# Sheet1.net
KiCad netlist of a schematic drawn in Altium Designer
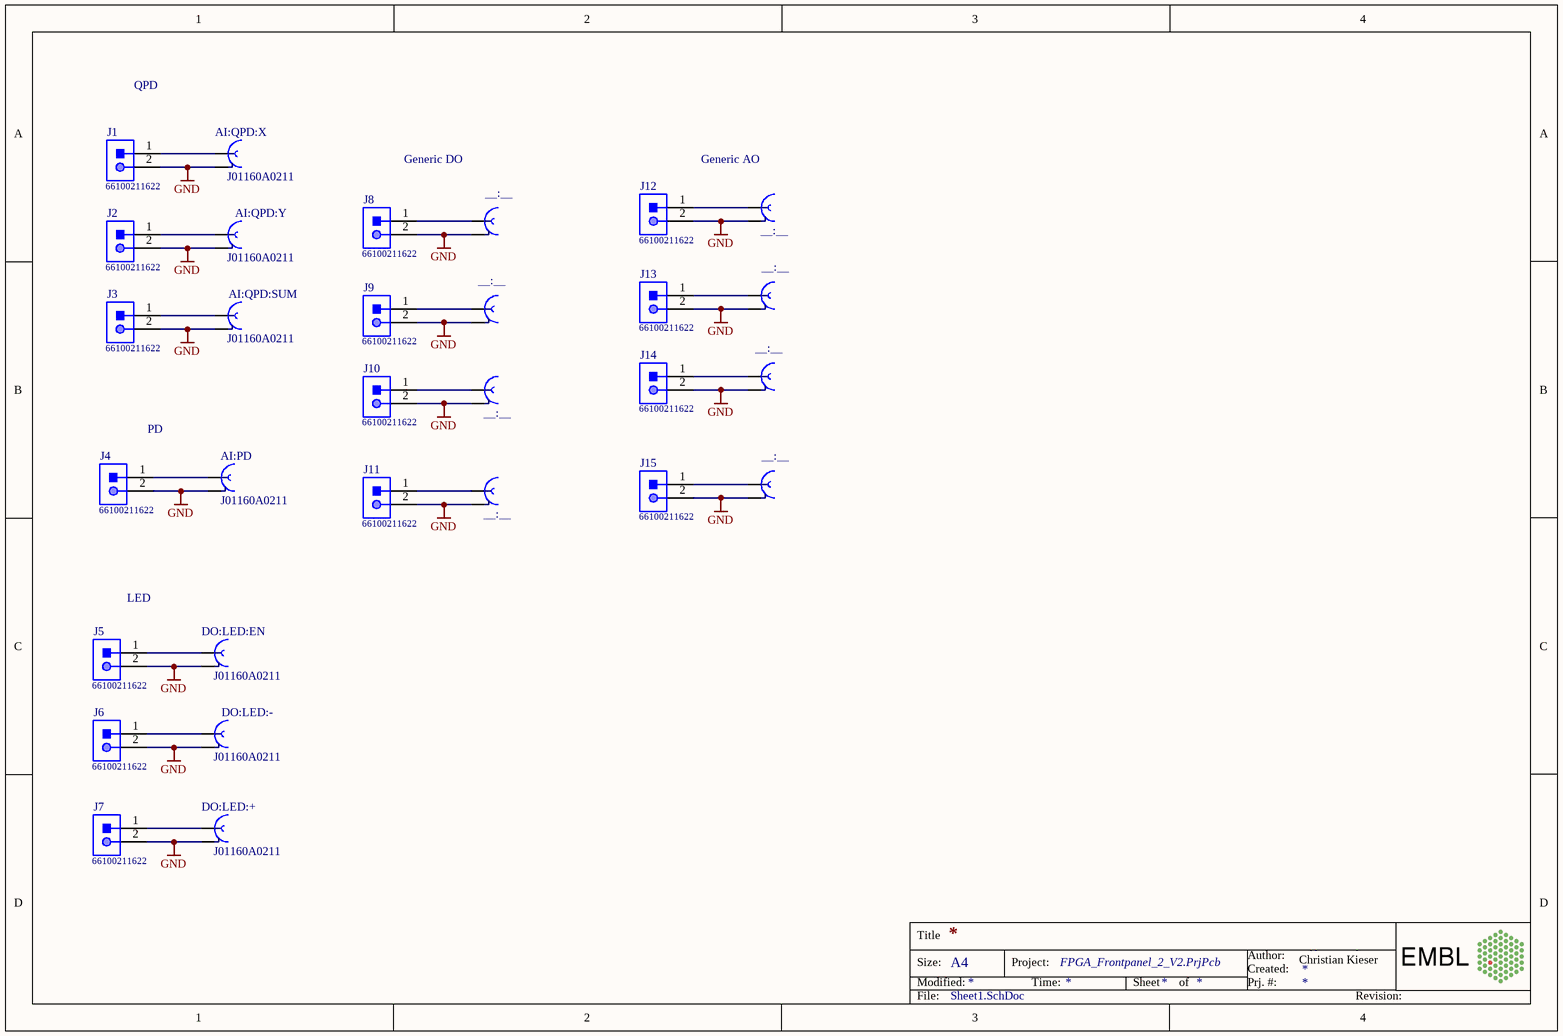
[diagram p0: Sheet1.SchDoc]

(export (version "E")
  (design (tool "Eeschema 10.0.6"))
  (components
    (comp (ref "AI:PD")
      (value "J01160A0211")
      (footprint "J01160A0211")
      (description "RF SMB Connector, Male, Board Mount, Solder Terminal, Receptacle")
      (libsource (lib "EMBL") (part "J01160A0211"))
    )
    (comp (ref "AI:QPD:SUM")
      (value "J01160A0211")
      (footprint "J01160A0211")
      (description "RF SMB Connector, Male, Board Mount, Solder Terminal, Receptacle")
      (libsource (lib "EMBL") (part "J01160A0211"))
    )
    (comp (ref "AI:QPD:X")
      (value "J01160A0211")
      (footprint "J01160A0211")
      (description "RF SMB Connector, Male, Board Mount, Solder Terminal, Receptacle")
      (libsource (lib "EMBL") (part "J01160A0211"))
    )
    (comp (ref "AI:QPD:Y")
      (value "J01160A0211")
      (footprint "J01160A0211")
      (description "RF SMB Connector, Male, Board Mount, Solder Terminal, Receptacle")
      (libsource (lib "EMBL") (part "J01160A0211"))
    )
    (comp (ref "DO:LED:+")
      (value "J01160A0211")
      (footprint "J01160A0211")
      (description "RF SMB Connector, Male, Board Mount, Solder Terminal, Receptacle")
      (libsource (lib "EMBL") (part "J01160A0211"))
    )
    (comp (ref "DO:LED:-")
      (value "J01160A0211")
      (footprint "J01160A0211")
      (description "RF SMB Connector, Male, Board Mount, Solder Terminal, Receptacle")
      (libsource (lib "EMBL") (part "J01160A0211"))
    )
    (comp (ref "DO:LED:EN")
      (value "J01160A0211")
      (footprint "J01160A0211")
      (description "RF SMB Connector, Male, Board Mount, Solder Terminal, Receptacle")
      (libsource (lib "EMBL") (part "J01160A0211"))
    )
    (comp (ref "J1")
      (value "66100211622")
      (footprint "66100211622")
      (description "WR-WTB 2.54 mm Male Vertical Shrouded Header 2 Pins")
      (fields (field (name "MANUFACTURER") "Wurth Electronics"))
      (libsource (lib "EMBL") (part "WE-CN-1P-M-R2"))
    )
    (comp (ref "J2")
      (value "66100211622")
      (footprint "66100211622")
      (description "WR-WTB 2.54 mm Male Vertical Shrouded Header 2 Pins")
      (fields (field (name "MANUFACTURER") "Wurth Electronics"))
      (libsource (lib "EMBL") (part "WE-CN-1P-M-R2"))
    )
    (comp (ref "J3")
      (value "66100211622")
      (footprint "66100211622")
      (description "WR-WTB 2.54 mm Male Vertical Shrouded Header 2 Pins")
      (fields (field (name "MANUFACTURER") "Wurth Electronics"))
      (libsource (lib "EMBL") (part "WE-CN-1P-M-R2"))
    )
    (comp (ref "J4")
      (value "66100211622")
      (footprint "66100211622")
      (description "WR-WTB 2.54 mm Male Vertical Shrouded Header 2 Pins")
      (fields (field (name "MANUFACTURER") "Wurth Electronics"))
      (libsource (lib "EMBL") (part "WE-CN-1P-M-R2"))
    )
    (comp (ref "J5")
      (value "66100211622")
      (footprint "66100211622")
      (description "WR-WTB 2.54 mm Male Vertical Shrouded Header 2 Pins")
      (fields (field (name "MANUFACTURER") "Wurth Electronics"))
      (libsource (lib "EMBL") (part "WE-CN-1P-M-R2"))
    )
    (comp (ref "J6")
      (value "66100211622")
      (footprint "66100211622")
      (description "WR-WTB 2.54 mm Male Vertical Shrouded Header 2 Pins")
      (fields (field (name "MANUFACTURER") "Wurth Electronics"))
      (libsource (lib "EMBL") (part "WE-CN-1P-M-R2"))
    )
    (comp (ref "J7")
      (value "66100211622")
      (footprint "66100211622")
      (description "WR-WTB 2.54 mm Male Vertical Shrouded Header 2 Pins")
      (fields (field (name "MANUFACTURER") "Wurth Electronics"))
      (libsource (lib "EMBL") (part "WE-CN-1P-M-R2"))
    )
    (comp (ref "J8")
      (value "66100211622")
      (footprint "66100211622")
      (description "WR-WTB 2.54 mm Male Vertical Shrouded Header 2 Pins")
      (fields (field (name "MANUFACTURER") "Wurth Electronics"))
      (libsource (lib "EMBL") (part "WE-CN-1P-M-R2"))
    )
    (comp (ref "J8_1")
      (value "__:__")
      (footprint "J01160A0211")
      (description "RF SMB Connector, Male, Board Mount, Solder Terminal, Receptacle")
      (libsource (lib "EMBL") (part "J01160A0211"))
    )
    (comp (ref "J9")
      (value "66100211622")
      (footprint "66100211622")
      (description "WR-WTB 2.54 mm Male Vertical Shrouded Header 2 Pins")
      (fields (field (name "MANUFACTURER") "Wurth Electronics"))
      (libsource (lib "EMBL") (part "WE-CN-1P-M-R2"))
    )
    (comp (ref "J9_1")
      (value "__:__")
      (footprint "J01160A0211")
      (description "RF SMB Connector, Male, Board Mount, Solder Terminal, Receptacle")
      (libsource (lib "EMBL") (part "J01160A0211"))
    )
    (comp (ref "J10")
      (value "66100211622")
      (footprint "66100211622")
      (description "WR-WTB 2.54 mm Male Vertical Shrouded Header 2 Pins")
      (fields (field (name "MANUFACTURER") "Wurth Electronics"))
      (libsource (lib "EMBL") (part "WE-CN-1P-M-R2"))
    )
    (comp (ref "J10_1")
      (value "__:__")
      (footprint "J01160A0211")
      (description "RF SMB Connector, Male, Board Mount, Solder Terminal, Receptacle")
      (libsource (lib "EMBL") (part "J01160A0211"))
    )
    (comp (ref "J11")
      (value "66100211622")
      (footprint "66100211622")
      (description "WR-WTB 2.54 mm Male Vertical Shrouded Header 2 Pins")
      (fields (field (name "MANUFACTURER") "Wurth Electronics"))
      (libsource (lib "EMBL") (part "WE-CN-1P-M-R2"))
    )
    (comp (ref "J11_1")
      (value "__:__")
      (footprint "J01160A0211")
      (description "RF SMB Connector, Male, Board Mount, Solder Terminal, Receptacle")
      (libsource (lib "EMBL") (part "J01160A0211"))
    )
    (comp (ref "J12")
      (value "66100211622")
      (footprint "66100211622")
      (description "WR-WTB 2.54 mm Male Vertical Shrouded Header 2 Pins")
      (fields (field (name "MANUFACTURER") "Wurth Electronics"))
      (libsource (lib "EMBL") (part "WE-CN-1P-M-R2"))
    )
    (comp (ref "J12_1")
      (value "__:__")
      (footprint "J01160A0211")
      (description "RF SMB Connector, Male, Board Mount, Solder Terminal, Receptacle")
      (libsource (lib "EMBL") (part "J01160A0211"))
    )
    (comp (ref "J13")
      (value "66100211622")
      (footprint "66100211622")
      (description "WR-WTB 2.54 mm Male Vertical Shrouded Header 2 Pins")
      (fields (field (name "MANUFACTURER") "Wurth Electronics"))
      (libsource (lib "EMBL") (part "WE-CN-1P-M-R2"))
    )
    (comp (ref "J13_1")
      (value "__:__")
      (footprint "J01160A0211")
      (description "RF SMB Connector, Male, Board Mount, Solder Terminal, Receptacle")
      (libsource (lib "EMBL") (part "J01160A0211"))
    )
    (comp (ref "J14")
      (value "66100211622")
      (footprint "66100211622")
      (description "WR-WTB 2.54 mm Male Vertical Shrouded Header 2 Pins")
      (fields (field (name "MANUFACTURER") "Wurth Electronics"))
      (libsource (lib "EMBL") (part "WE-CN-1P-M-R2"))
    )
    (comp (ref "J14_1")
      (value "__:__")
      (footprint "J01160A0211")
      (description "RF SMB Connector, Male, Board Mount, Solder Terminal, Receptacle")
      (libsource (lib "EMBL") (part "J01160A0211"))
    )
    (comp (ref "J15")
      (value "66100211622")
      (footprint "66100211622")
      (description "WR-WTB 2.54 mm Male Vertical Shrouded Header 2 Pins")
      (fields (field (name "MANUFACTURER") "Wurth Electronics"))
      (libsource (lib "EMBL") (part "WE-CN-1P-M-R2"))
    )
    (comp (ref "J15_1")
      (value "__:__")
      (footprint "J01160A0211")
      (description "RF SMB Connector, Male, Board Mount, Solder Terminal, Receptacle")
      (libsource (lib "EMBL") (part "J01160A0211"))
    )
  )
  (nets
    (net (code "1") (name "GND") (class "Default")
      (node (ref "AI:PD") (pin "2") (pinfunction "2_2") (pintype "passive"))
      (node (ref "AI:QPD:SUM") (pin "2") (pinfunction "2_2") (pintype "passive"))
      (node (ref "AI:QPD:X") (pin "2") (pinfunction "2_2") (pintype "passive"))
      (node (ref "AI:QPD:Y") (pin "2") (pinfunction "2_2") (pintype "passive"))
      (node (ref "DO:LED:+") (pin "2") (pinfunction "2_2") (pintype "passive"))
      (node (ref "DO:LED:-") (pin "2") (pinfunction "2_2") (pintype "passive"))
      (node (ref "DO:LED:EN") (pin "2") (pinfunction "2_2") (pintype "passive"))
      (node (ref "J1") (pin "2") (pinfunction "2_2") (pintype "passive"))
      (node (ref "J10") (pin "2") (pinfunction "2_2") (pintype "passive"))
      (node (ref "J10_1") (pin "2") (pinfunction "2_2") (pintype "passive"))
      (node (ref "J11") (pin "2") (pinfunction "2_2") (pintype "passive"))
      (node (ref "J11_1") (pin "2") (pinfunction "2_2") (pintype "passive"))
      (node (ref "J12") (pin "2") (pinfunction "2_2") (pintype "passive"))
      (node (ref "J12_1") (pin "2") (pinfunction "2_2") (pintype "passive"))
      (node (ref "J13") (pin "2") (pinfunction "2_2") (pintype "passive"))
      (node (ref "J13_1") (pin "2") (pinfunction "2_2") (pintype "passive"))
      (node (ref "J14") (pin "2") (pinfunction "2_2") (pintype "passive"))
      (node (ref "J14_1") (pin "2") (pinfunction "2_2") (pintype "passive"))
      (node (ref "J15") (pin "2") (pinfunction "2_2") (pintype "passive"))
      (node (ref "J15_1") (pin "2") (pinfunction "2_2") (pintype "passive"))
      (node (ref "J2") (pin "2") (pinfunction "2_2") (pintype "passive"))
      (node (ref "J3") (pin "2") (pinfunction "2_2") (pintype "passive"))
      (node (ref "J4") (pin "2") (pinfunction "2_2") (pintype "passive"))
      (node (ref "J5") (pin "2") (pinfunction "2_2") (pintype "passive"))
      (node (ref "J6") (pin "2") (pinfunction "2_2") (pintype "passive"))
      (node (ref "J7") (pin "2") (pinfunction "2_2") (pintype "passive"))
      (node (ref "J8") (pin "2") (pinfunction "2_2") (pintype "passive"))
      (node (ref "J8_1") (pin "2") (pinfunction "2_2") (pintype "passive"))
      (node (ref "J9") (pin "2") (pinfunction "2_2") (pintype "passive"))
      (node (ref "J9_1") (pin "2") (pinfunction "2_2") (pintype "passive"))
    )
    (net (code "2") (name "Net-(AI:PD-Pad1)") (class "Default")
      (node (ref "AI:PD") (pin "1") (pinfunction "1_1") (pintype "passive"))
      (node (ref "J4") (pin "1") (pinfunction "1_1") (pintype "passive"))
    )
    (net (code "3") (name "Net-(AI:QPD:SUM-Pad1)") (class "Default")
      (node (ref "AI:QPD:SUM") (pin "1") (pinfunction "1_1") (pintype "passive"))
      (node (ref "J3") (pin "1") (pinfunction "1_1") (pintype "passive"))
    )
    (net (code "4") (name "Net-(AI:QPD:X-Pad1)") (class "Default")
      (node (ref "AI:QPD:X") (pin "1") (pinfunction "1_1") (pintype "passive"))
      (node (ref "J1") (pin "1") (pinfunction "1_1") (pintype "passive"))
    )
    (net (code "5") (name "Net-(AI:QPD:Y-Pad1)") (class "Default")
      (node (ref "AI:QPD:Y") (pin "1") (pinfunction "1_1") (pintype "passive"))
      (node (ref "J2") (pin "1") (pinfunction "1_1") (pintype "passive"))
    )
    (net (code "6") (name "Net-(DO:LED:+-Pad1)") (class "Default")
      (node (ref "DO:LED:+") (pin "1") (pinfunction "1_1") (pintype "passive"))
      (node (ref "J7") (pin "1") (pinfunction "1_1") (pintype "passive"))
    )
    (net (code "7") (name "Net-(DO:LED:--Pad1)") (class "Default")
      (node (ref "DO:LED:-") (pin "1") (pinfunction "1_1") (pintype "passive"))
      (node (ref "J6") (pin "1") (pinfunction "1_1") (pintype "passive"))
    )
    (net (code "8") (name "Net-(DO:LED:EN-Pad1)") (class "Default")
      (node (ref "DO:LED:EN") (pin "1") (pinfunction "1_1") (pintype "passive"))
      (node (ref "J5") (pin "1") (pinfunction "1_1") (pintype "passive"))
    )
    (net (code "9") (name "Net-(J8-Pad1)") (class "Default")
      (node (ref "J8") (pin "1") (pinfunction "1_1") (pintype "passive"))
      (node (ref "J8_1") (pin "1") (pinfunction "1_1") (pintype "passive"))
    )
    (net (code "10") (name "Net-(J9-Pad1)") (class "Default")
      (node (ref "J9") (pin "1") (pinfunction "1_1") (pintype "passive"))
      (node (ref "J9_1") (pin "1") (pinfunction "1_1") (pintype "passive"))
    )
    (net (code "11") (name "Net-(J10-Pad1)") (class "Default")
      (node (ref "J10") (pin "1") (pinfunction "1_1") (pintype "passive"))
      (node (ref "J10_1") (pin "1") (pinfunction "1_1") (pintype "passive"))
    )
    (net (code "12") (name "Net-(J11-Pad1)") (class "Default")
      (node (ref "J11") (pin "1") (pinfunction "1_1") (pintype "passive"))
      (node (ref "J11_1") (pin "1") (pinfunction "1_1") (pintype "passive"))
    )
    (net (code "13") (name "Net-(J12-Pad1)") (class "Default")
      (node (ref "J12") (pin "1") (pinfunction "1_1") (pintype "passive"))
      (node (ref "J12_1") (pin "1") (pinfunction "1_1") (pintype "passive"))
    )
    (net (code "14") (name "Net-(J13-Pad1)") (class "Default")
      (node (ref "J13") (pin "1") (pinfunction "1_1") (pintype "passive"))
      (node (ref "J13_1") (pin "1") (pinfunction "1_1") (pintype "passive"))
    )
    (net (code "15") (name "Net-(J14-Pad1)") (class "Default")
      (node (ref "J14") (pin "1") (pinfunction "1_1") (pintype "passive"))
      (node (ref "J14_1") (pin "1") (pinfunction "1_1") (pintype "passive"))
    )
    (net (code "16") (name "Net-(J15-Pad1)") (class "Default")
      (node (ref "J15") (pin "1") (pinfunction "1_1") (pintype "passive"))
      (node (ref "J15_1") (pin "1") (pinfunction "1_1") (pintype "passive"))
    )
  )
)
